# NanoGwSchm.net
KiCad netlist of a schematic drawn in EAGLE
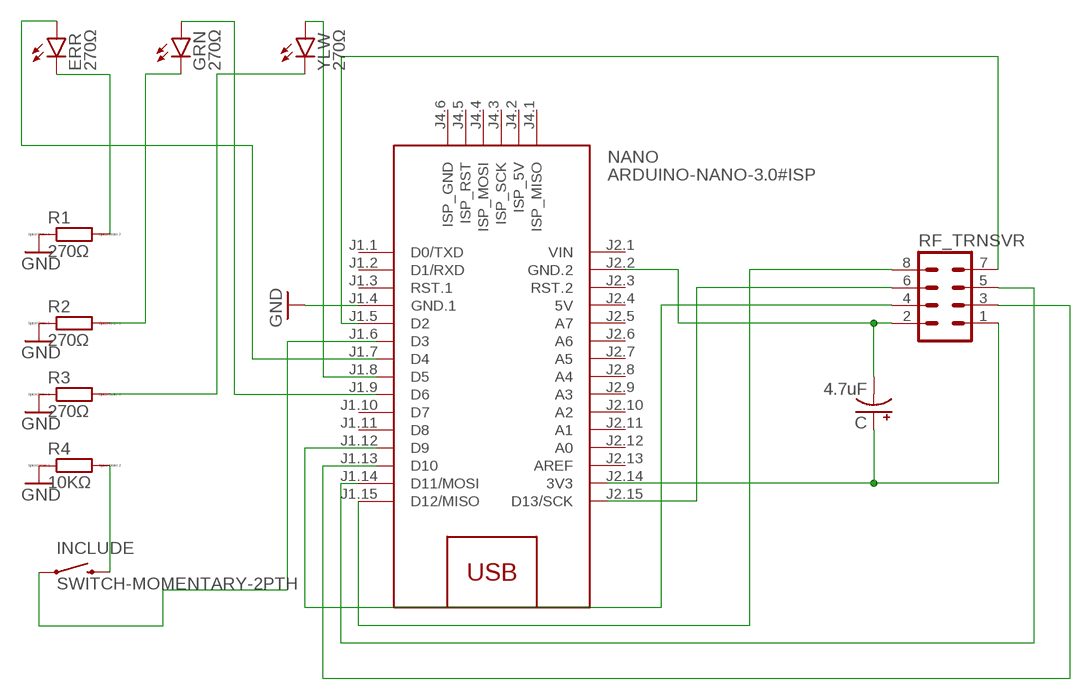
[diagram p0: schematic, sheet 1]

(export (version "E")
  (design (tool "Eeschema 10.0.6"))
  (components
    (comp (ref "C")
      (value "4.7uF")
      (footprint "eagle-import:E2-5")
      (libsource (lib "eagle-import") (part "CPOL-USE2-5"))
    )
    (comp (ref "ERR")
      (value "270Ω")
      (footprint "eagle-import:LED5MM")
      (libsource (lib "eagle-import") (part "LED5MM"))
    )
    (comp (ref "GRN")
      (value "270Ω")
      (footprint "eagle-import:LED5MM")
      (libsource (lib "eagle-import") (part "LED5MM"))
    )
    (comp (ref "INCLUDE")
      (value "SWITCH-MOMENTARY-2PTH")
      (footprint "eagle-import:TACTILE-PTH")
      (libsource (lib "eagle-import") (part "SWITCH-MOMENTARY-2PTH"))
    )
    (comp (ref "NANO")
      (value "ARDUINO-NANO-3.0#ISP")
      (footprint "eagle-import:ARDUINO-NANO-3.0#ISP")
      (libsource (lib "eagle-import") (part "ARDUINO-NANO-3.0#ISP"))
    )
    (comp (ref "R1")
      (value "270Ω")
      (footprint "eagle-import:0204_7")
      (libsource (lib "eagle-import") (part "R0204/7"))
    )
    (comp (ref "R2")
      (value "270Ω")
      (footprint "eagle-import:0204_7")
      (libsource (lib "eagle-import") (part "R0204/7"))
    )
    (comp (ref "R3")
      (value "270Ω")
      (footprint "eagle-import:0204_7")
      (libsource (lib "eagle-import") (part "R0204/7"))
    )
    (comp (ref "R4")
      (value "10KΩ")
      (footprint "eagle-import:0204_7")
      (libsource (lib "eagle-import") (part "R0204/7"))
    )
    (comp (ref "RF_TRNSVR")
      (value "MA04-2")
      (footprint "eagle-import:MA04-2")
      (libsource (lib "eagle-import") (part "MA04-2"))
    )
    (comp (ref "YLW")
      (value "270Ω")
      (footprint "eagle-import:LED5MM")
      (libsource (lib "eagle-import") (part "LED5MM"))
    )
  )
  (nets
    (net (code "1") (name "/3V3") (class "Default")
      (node (ref "NANO") (pin "J2.14") (pinfunction "3V3_J2.14") (pintype "power_in"))
    )
    (net (code "2") (name "/5V") (class "Default")
      (node (ref "NANO") (pin "J2.4") (pinfunction "5V_J2.4") (pintype "power_in"))
    )
    (net (code "3") (name "/VIN") (class "Default")
      (node (ref "NANO") (pin "J2.1") (pinfunction "VIN_J2.1") (pintype "power_in"))
    )
    (net (code "4") (name "GND") (class "Default")
      (node (ref "NANO") (pin "J1.4") (pinfunction "GND.1_J1.4") (pintype "power_in"))
      (node (ref "R1") (pin "1") (pinfunction "1_1") (pintype "passive"))
      (node (ref "R2") (pin "1") (pinfunction "1_1") (pintype "passive"))
      (node (ref "R3") (pin "1") (pinfunction "1_1") (pintype "passive"))
      (node (ref "R4") (pin "1") (pinfunction "1_1") (pintype "passive"))
    )
    (net (code "5") (name "Net-(C-Pad+)") (class "Default")
      (node (ref "C") (pin "+") (pinfunction "+_+") (pintype "passive"))
      (node (ref "RF_TRNSVR") (pin "1") (pinfunction "1_1") (pintype "passive"))
    )
    (net (code "6") (name "Net-(ERR-C)") (class "Default")
      (node (ref "ERR") (pin "K") (pinfunction "C_K") (pintype "passive"))
      (node (ref "R1") (pin "2") (pinfunction "2_2") (pintype "passive"))
    )
    (net (code "7") (name "Net-(GRN-C)") (class "Default")
      (node (ref "GRN") (pin "K") (pinfunction "C_K") (pintype "passive"))
      (node (ref "R2") (pin "2") (pinfunction "2_2") (pintype "passive"))
    )
    (net (code "8") (name "Net-(INCLUDE-2)") (class "Default")
      (node (ref "INCLUDE") (pin "3") (pinfunction "2_3") (pintype "passive"))
      (node (ref "R4") (pin "2") (pinfunction "2_2") (pintype "passive"))
    )
    (net (code "9") (name "Net-(NANO-D2)") (class "Default")
      (node (ref "NANO") (pin "J1.5") (pinfunction "D2_J1.5") (pintype "bidirectional"))
      (node (ref "RF_TRNSVR") (pin "7") (pinfunction "7_7") (pintype "passive"))
    )
    (net (code "10") (name "Net-(NANO-D11{slash}MOSI)") (class "Default")
      (node (ref "NANO") (pin "J1.14") (pinfunction "D11/MOSI_J1.14") (pintype "bidirectional"))
      (node (ref "RF_TRNSVR") (pin "5") (pinfunction "5_5") (pintype "passive"))
    )
    (net (code "11") (name "Net-(NANO-D12{slash}MISO)") (class "Default")
      (node (ref "NANO") (pin "J1.15") (pinfunction "D12/MISO_J1.15") (pintype "bidirectional"))
      (node (ref "RF_TRNSVR") (pin "8") (pinfunction "8_8") (pintype "passive"))
    )
    (net (code "12") (name "Net-(NANO-GND.2)") (class "Default")
      (node (ref "C") (pin "-") (pinfunction "-_-") (pintype "passive"))
      (node (ref "NANO") (pin "J2.2") (pinfunction "GND.2_J2.2") (pintype "power_in"))
      (node (ref "RF_TRNSVR") (pin "2") (pinfunction "2_2") (pintype "passive"))
    )
    (net (code "13") (name "Net-(YLW-C)") (class "Default")
      (node (ref "R3") (pin "2") (pinfunction "2_2") (pintype "passive"))
      (node (ref "YLW") (pin "K") (pinfunction "C_K") (pintype "passive"))
    )
    (net (code "14") (name "unconnected-(ERR-PadA)") (class "Default")
      (node (ref "ERR") (pin "A") (pinfunction "A_A") (pintype "passive"))
    )
    (net (code "15") (name "unconnected-(GRN-PadA)") (class "Default")
      (node (ref "GRN") (pin "A") (pinfunction "A_A") (pintype "passive"))
    )
    (net (code "16") (name "unconnected-(INCLUDE-Pad1)") (class "Default")
      (node (ref "INCLUDE") (pin "1") (pinfunction "1_1") (pintype "passive"))
    )
    (net (code "17") (name "unconnected-(NANO-A0-PadJ2.12)") (class "Default")
      (node (ref "NANO") (pin "J2.12") (pinfunction "A0_J2.12") (pintype "bidirectional"))
    )
    (net (code "18") (name "unconnected-(NANO-A1-PadJ2.11)") (class "Default")
      (node (ref "NANO") (pin "J2.11") (pinfunction "A1_J2.11") (pintype "bidirectional"))
    )
    (net (code "19") (name "unconnected-(NANO-A2-PadJ2.10)") (class "Default")
      (node (ref "NANO") (pin "J2.10") (pinfunction "A2_J2.10") (pintype "bidirectional"))
    )
    (net (code "20") (name "unconnected-(NANO-A3-PadJ2.9)") (class "Default")
      (node (ref "NANO") (pin "J2.9") (pinfunction "A3_J2.9") (pintype "bidirectional"))
    )
    (net (code "21") (name "unconnected-(NANO-A4-PadJ2.8)") (class "Default")
      (node (ref "NANO") (pin "J2.8") (pinfunction "A4_J2.8") (pintype "bidirectional"))
    )
    (net (code "22") (name "unconnected-(NANO-A5-PadJ2.7)") (class "Default")
      (node (ref "NANO") (pin "J2.7") (pinfunction "A5_J2.7") (pintype "bidirectional"))
    )
    (net (code "23") (name "unconnected-(NANO-A6-PadJ2.6)") (class "Default")
      (node (ref "NANO") (pin "J2.6") (pinfunction "A6_J2.6") (pintype "bidirectional"))
    )
    (net (code "24") (name "unconnected-(NANO-A7-PadJ2.5)") (class "Default")
      (node (ref "NANO") (pin "J2.5") (pinfunction "A7_J2.5") (pintype "bidirectional"))
    )
    (net (code "25") (name "unconnected-(NANO-AREF-PadJ2.13)") (class "Default")
      (node (ref "NANO") (pin "J2.13") (pinfunction "AREF_J2.13") (pintype "bidirectional"))
    )
    (net (code "26") (name "unconnected-(NANO-D0{slash}TXD-PadJ1.1)") (class "Default")
      (node (ref "NANO") (pin "J1.1") (pinfunction "D0/TXD_J1.1") (pintype "bidirectional"))
    )
    (net (code "27") (name "unconnected-(NANO-D1{slash}RXD-PadJ1.2)") (class "Default")
      (node (ref "NANO") (pin "J1.2") (pinfunction "D1/RXD_J1.2") (pintype "bidirectional"))
    )
    (net (code "28") (name "unconnected-(NANO-D3-PadJ1.6)") (class "Default")
      (node (ref "NANO") (pin "J1.6") (pinfunction "D3_J1.6") (pintype "bidirectional"))
    )
    (net (code "29") (name "unconnected-(NANO-D4-PadJ1.7)") (class "Default")
      (node (ref "NANO") (pin "J1.7") (pinfunction "D4_J1.7") (pintype "bidirectional"))
    )
    (net (code "30") (name "unconnected-(NANO-D5-PadJ1.8)") (class "Default")
      (node (ref "NANO") (pin "J1.8") (pinfunction "D5_J1.8") (pintype "bidirectional"))
    )
    (net (code "31") (name "unconnected-(NANO-D6-PadJ1.9)") (class "Default")
      (node (ref "NANO") (pin "J1.9") (pinfunction "D6_J1.9") (pintype "bidirectional"))
    )
    (net (code "32") (name "unconnected-(NANO-D7-PadJ1.10)") (class "Default")
      (node (ref "NANO") (pin "J1.10") (pinfunction "D7_J1.10") (pintype "bidirectional"))
    )
    (net (code "33") (name "unconnected-(NANO-D8-PadJ1.11)") (class "Default")
      (node (ref "NANO") (pin "J1.11") (pinfunction "D8_J1.11") (pintype "bidirectional"))
    )
    (net (code "34") (name "unconnected-(NANO-D9-PadJ1.12)") (class "Default")
      (node (ref "NANO") (pin "J1.12") (pinfunction "D9_J1.12") (pintype "bidirectional"))
    )
    (net (code "35") (name "unconnected-(NANO-D10-PadJ1.13)") (class "Default")
      (node (ref "NANO") (pin "J1.13") (pinfunction "D10_J1.13") (pintype "bidirectional"))
    )
    (net (code "36") (name "unconnected-(NANO-D13{slash}SCK-PadJ2.15)") (class "Default")
      (node (ref "NANO") (pin "J2.15") (pinfunction "D13/SCK_J2.15") (pintype "bidirectional"))
    )
    (net (code "37") (name "unconnected-(NANO-ISP_5V-PadJ4.2)") (class "Default")
      (node (ref "NANO") (pin "J4.2") (pinfunction "ISP_5V_J4.2") (pintype "bidirectional"))
    )
    (net (code "38") (name "unconnected-(NANO-ISP_GND-PadJ4.6)") (class "Default")
      (node (ref "NANO") (pin "J4.6") (pinfunction "ISP_GND_J4.6") (pintype "bidirectional"))
    )
    (net (code "39") (name "unconnected-(NANO-ISP_MISO-PadJ4.1)") (class "Default")
      (node (ref "NANO") (pin "J4.1") (pinfunction "ISP_MISO_J4.1") (pintype "bidirectional"))
    )
    (net (code "40") (name "unconnected-(NANO-ISP_MOSI-PadJ4.4)") (class "Default")
      (node (ref "NANO") (pin "J4.4") (pinfunction "ISP_MOSI_J4.4") (pintype "bidirectional"))
    )
    (net (code "41") (name "unconnected-(NANO-ISP_RST-PadJ4.5)") (class "Default")
      (node (ref "NANO") (pin "J4.5") (pinfunction "ISP_RST_J4.5") (pintype "bidirectional"))
    )
    (net (code "42") (name "unconnected-(NANO-ISP_SCK-PadJ4.3)") (class "Default")
      (node (ref "NANO") (pin "J4.3") (pinfunction "ISP_SCK_J4.3") (pintype "bidirectional"))
    )
    (net (code "43") (name "unconnected-(NANO-RST.1-PadJ1.3)") (class "Default")
      (node (ref "NANO") (pin "J1.3") (pinfunction "RST.1_J1.3") (pintype "bidirectional"))
    )
    (net (code "44") (name "unconnected-(NANO-RST.2-PadJ2.3)") (class "Default")
      (node (ref "NANO") (pin "J2.3") (pinfunction "RST.2_J2.3") (pintype "bidirectional"))
    )
    (net (code "45") (name "unconnected-(RF_TRNSVR-Pad3)") (class "Default")
      (node (ref "RF_TRNSVR") (pin "3") (pinfunction "3_3") (pintype "passive"))
    )
    (net (code "46") (name "unconnected-(RF_TRNSVR-Pad4)") (class "Default")
      (node (ref "RF_TRNSVR") (pin "4") (pinfunction "4_4") (pintype "passive"))
    )
    (net (code "47") (name "unconnected-(RF_TRNSVR-Pad6)") (class "Default")
      (node (ref "RF_TRNSVR") (pin "6") (pinfunction "6_6") (pintype "passive"))
    )
    (net (code "48") (name "unconnected-(YLW-PadA)") (class "Default")
      (node (ref "YLW") (pin "A") (pinfunction "A_A") (pintype "passive"))
    )
  )
)
